# Power.net
KiCad netlist of a schematic drawn in Altium Designer
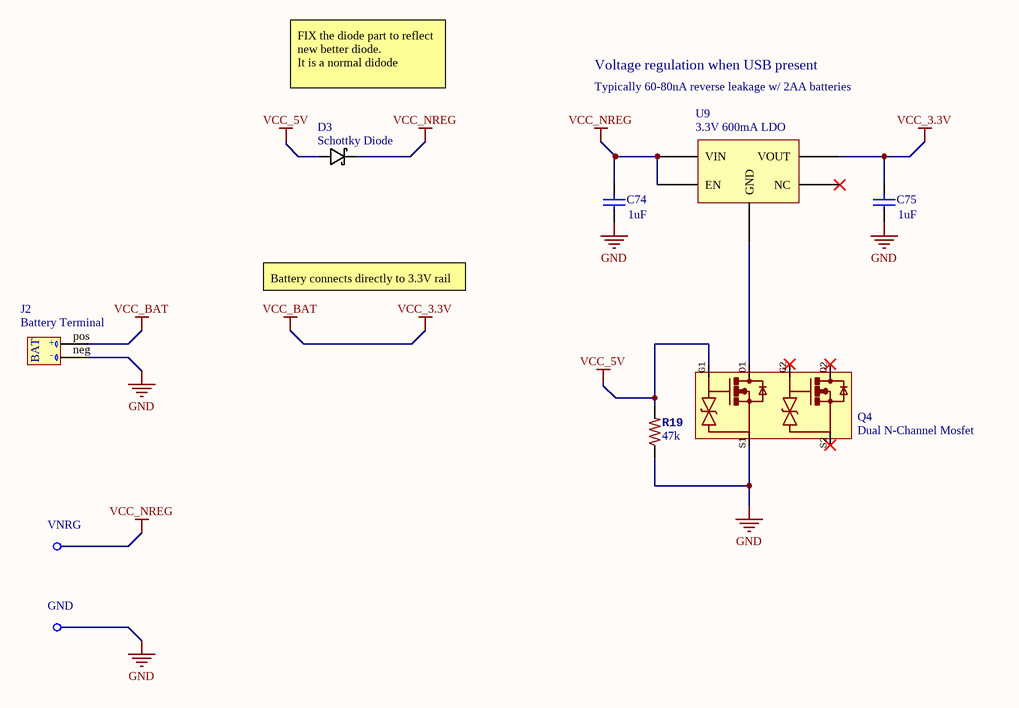
[diagram p0: Power.SchDoc]

(export (version "E")
  (design (tool "Eeschema 10.0.6"))
  (components
    (comp (ref "C74")
      (value "1uF")
      (footprint "1608[0603]")
      (description "Capacitor (Semiconductor SIM Model)")
      (fields (field (name "Comment") "Cap Semi") (field (name "PUBLISHER") "Altium Limited"))
      (libsource (lib "Miscellaneous Devices") (part "Cap Semi"))
    )
    (comp (ref "C75")
      (value "1uF")
      (footprint "1608[0603]")
      (description "Capacitor (Semiconductor SIM Model)")
      (fields (field (name "Comment") "Cap Semi") (field (name "PUBLISHER") "Altium Limited"))
      (libsource (lib "Miscellaneous Devices") (part "Cap Semi"))
    )
    (comp (ref "D3")
      (value "Schottky Diode")
      (footprint "DB2J20900L (high-density)")
      (description "Schottky Diode BAS 52-02V H6327")
      (libsource (lib "ExtraComponents") (part "DB2J20900L"))
    )
    (comp (ref "GND")
      (value "Test Pin")
      (footprint "pin_1mm")
      (libsource (lib "SX1276_e268v01a") (part "test_pin"))
    )
    (comp (ref "J2")
      (value "Battery Terminal")
      (footprint "Battery Terminal")
      (libsource (lib "ExtraComponents") (part "Battery Terminal"))
    )
    (comp (ref "Q4")
      (value "Dual N-Channel Mosfet")
      (footprint "FC6946010R (high-density)")
      (description "Panasonic Dual N-Channel Moseft FC6946010R")
      (libsource (lib "ExtraComponents") (part "FC6946010R"))
    )
    (comp (ref "R19")
      (value "47k")
      (footprint "0603-RES")
      (fields (field (name "Comment") "RES-00818"))
      (libsource (lib "SparkFun-Resistors") (part "330OHM1/10W1%(0603)"))
    )
    (comp (ref "U9")
      (value "3.3V 600mA LDO")
      (footprint "AP7365-SOT25 (high-density)")
      (description "AP7365-33WG-7 3.9V 600mA LDO")
      (libsource (lib "ExtraComponents") (part "AP7365-33WG-7"))
    )
    (comp (ref "VNRG")
      (value "~")
      (footprint "pin_1mm")
      (description "Voltage Non-Regulated")
      (libsource (lib "SX1276_e268v01a") (part "test_pin"))
    )
  )
  (nets
    (net (code "1") (name "GND") (class "Default")
      (node (ref "C74") (pin "1") (pinfunction "1_1") (pintype "passive"))
      (node (ref "C75") (pin "1") (pinfunction "1_1") (pintype "passive"))
      (node (ref "GND") (pin "1") (pinfunction "pin_1") (pintype "passive"))
      (node (ref "J2") (pin "neg") (pinfunction "neg_neg") (pintype "passive"))
      (node (ref "Q4") (pin "S1") (pinfunction "S1_S1") (pintype "passive"))
      (node (ref "R19") (pin "1") (pinfunction "1_1") (pintype "passive"))
    )
    (net (code "2") (name "Net-(Q4-PadD1)") (class "Default")
      (node (ref "Q4") (pin "D1") (pinfunction "D1_D1") (pintype "passive"))
      (node (ref "U9") (pin "GND") (pinfunction "GND_GND") (pintype "passive"))
    )
    (net (code "3") (name "VCC_3.3V") (class "Default")
      (node (ref "C75") (pin "2") (pinfunction "2_2") (pintype "passive"))
      (node (ref "J2") (pin "pos") (pinfunction "pos_pos") (pintype "passive"))
      (node (ref "U9") (pin "VOUT") (pinfunction "VOUT_VOUT") (pintype "passive"))
    )
    (net (code "4") (name "VCC_5V") (class "Default")
      (node (ref "D3") (pin "2") (pinfunction "2_2") (pintype "passive"))
      (node (ref "Q4") (pin "G1") (pinfunction "G1_G1") (pintype "passive"))
      (node (ref "R19") (pin "2") (pinfunction "2_2") (pintype "passive"))
    )
    (net (code "5") (name "VCC_NREG") (class "Default")
      (node (ref "C74") (pin "2") (pinfunction "2_2") (pintype "passive"))
      (node (ref "D3") (pin "1") (pinfunction "1_1") (pintype "passive"))
      (node (ref "U9") (pin "EN") (pinfunction "EN_EN") (pintype "passive"))
      (node (ref "U9") (pin "VIN") (pinfunction "VIN_VIN") (pintype "passive"))
      (node (ref "VNRG") (pin "1") (pinfunction "pin_1") (pintype "passive"))
    )
    (net (code "6") (name "unconnected-(Q4-PadD2)") (class "Default")
      (node (ref "Q4") (pin "D2") (pinfunction "D2_D2") (pintype "passive+no_connect"))
    )
    (net (code "7") (name "unconnected-(Q4-PadG2)") (class "Default")
      (node (ref "Q4") (pin "G2") (pinfunction "G2_G2") (pintype "passive+no_connect"))
    )
    (net (code "8") (name "unconnected-(Q4-PadS2)") (class "Default")
      (node (ref "Q4") (pin "S2") (pinfunction "S2_S2") (pintype "passive+no_connect"))
    )
    (net (code "9") (name "unconnected-(U9-PadNC)") (class "Default")
      (node (ref "U9") (pin "NC") (pinfunction "NC_NC") (pintype "passive+no_connect"))
    )
  )
)
